# interlinkP2B.net
KiCad netlist of a schematic drawn in Altium Designer
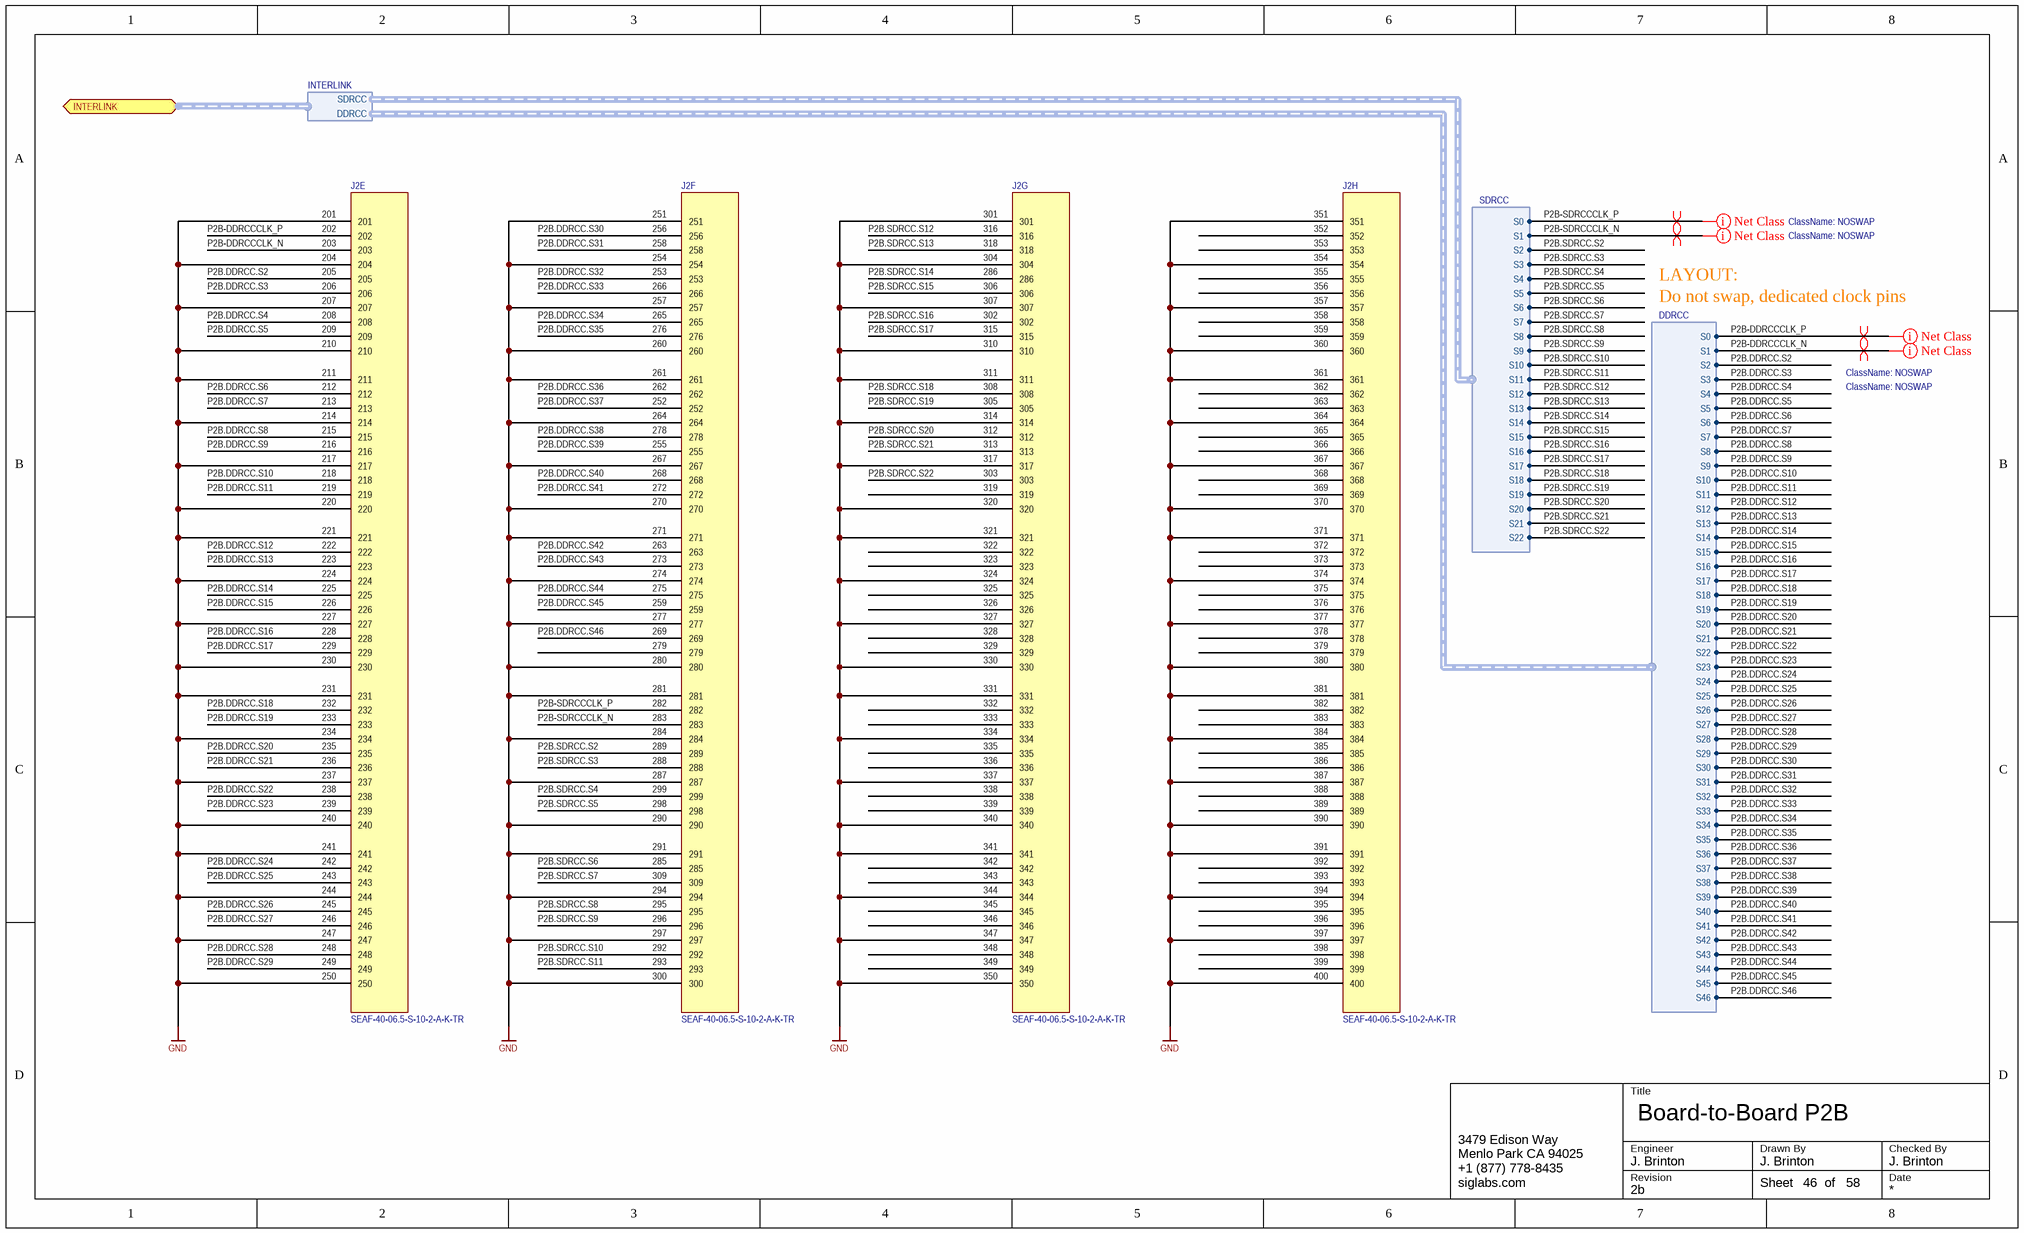
[diagram p0: interlinkP2B.SchDoc]

(export (version "E")
  (design (tool "Eeschema 10.0.6"))
  (components
    (comp (ref "J2")
      (value "SEAF-40-06.5-S-10-2-A-K-TR")
      (footprint "samtec:SEAF-40-06.5-S-10-2-A-K-TR")
      (description "Terminal Array Assembly, Surface Mount, 0.050\" Pitch, 400 Pins")
      (fields (field (name "MANUFACTURER") "Samtec"))
      (libsource (lib "samtec") (part "SEAF-40-06.5-S-10-2-A-K-TR"))
    )
  )
  (nets
    (net (code "4") (name "/P2B-DDRCCCLK_N") (class "Default")
      (node (ref "J2") (pin "203") (pinfunction "203_203") (pintype "passive"))
    )
    (net (code "5") (name "/P2B-DDRCCCLK_P") (class "Default")
      (node (ref "J2") (pin "202") (pinfunction "202_202") (pintype "passive"))
    )
    (net (code "6") (name "/P2B-SDRCCCLK_N") (class "Default")
      (node (ref "J2") (pin "283") (pinfunction "283_283") (pintype "passive"))
    )
    (net (code "7") (name "/P2B-SDRCCCLK_P") (class "Default")
      (node (ref "J2") (pin "282") (pinfunction "282_282") (pintype "passive"))
    )
    (net (code "8") (name "/P2B.DDRCC.S2") (class "Default")
      (node (ref "J2") (pin "205") (pinfunction "205_205") (pintype "passive"))
    )
    (net (code "9") (name "/P2B.DDRCC.S3") (class "Default")
      (node (ref "J2") (pin "206") (pinfunction "206_206") (pintype "passive"))
    )
    (net (code "10") (name "/P2B.DDRCC.S4") (class "Default")
      (node (ref "J2") (pin "208") (pinfunction "208_208") (pintype "passive"))
    )
    (net (code "11") (name "/P2B.DDRCC.S5") (class "Default")
      (node (ref "J2") (pin "209") (pinfunction "209_209") (pintype "passive"))
    )
    (net (code "12") (name "/P2B.DDRCC.S6") (class "Default")
      (node (ref "J2") (pin "212") (pinfunction "212_212") (pintype "passive"))
    )
    (net (code "13") (name "/P2B.DDRCC.S7") (class "Default")
      (node (ref "J2") (pin "213") (pinfunction "213_213") (pintype "passive"))
    )
    (net (code "14") (name "/P2B.DDRCC.S8") (class "Default")
      (node (ref "J2") (pin "215") (pinfunction "215_215") (pintype "passive"))
    )
    (net (code "15") (name "/P2B.DDRCC.S9") (class "Default")
      (node (ref "J2") (pin "216") (pinfunction "216_216") (pintype "passive"))
    )
    (net (code "16") (name "/P2B.DDRCC.S10") (class "Default")
      (node (ref "J2") (pin "218") (pinfunction "218_218") (pintype "passive"))
    )
    (net (code "17") (name "/P2B.DDRCC.S11") (class "Default")
      (node (ref "J2") (pin "219") (pinfunction "219_219") (pintype "passive"))
    )
    (net (code "18") (name "/P2B.DDRCC.S12") (class "Default")
      (node (ref "J2") (pin "222") (pinfunction "222_222") (pintype "passive"))
    )
    (net (code "19") (name "/P2B.DDRCC.S13") (class "Default")
      (node (ref "J2") (pin "223") (pinfunction "223_223") (pintype "passive"))
    )
    (net (code "20") (name "/P2B.DDRCC.S14") (class "Default")
      (node (ref "J2") (pin "225") (pinfunction "225_225") (pintype "passive"))
    )
    (net (code "21") (name "/P2B.DDRCC.S15") (class "Default")
      (node (ref "J2") (pin "226") (pinfunction "226_226") (pintype "passive"))
    )
    (net (code "22") (name "/P2B.DDRCC.S16") (class "Default")
      (node (ref "J2") (pin "228") (pinfunction "228_228") (pintype "passive"))
    )
    (net (code "23") (name "/P2B.DDRCC.S17") (class "Default")
      (node (ref "J2") (pin "229") (pinfunction "229_229") (pintype "passive"))
    )
    (net (code "24") (name "/P2B.DDRCC.S18") (class "Default")
      (node (ref "J2") (pin "232") (pinfunction "232_232") (pintype "passive"))
    )
    (net (code "25") (name "/P2B.DDRCC.S19") (class "Default")
      (node (ref "J2") (pin "233") (pinfunction "233_233") (pintype "passive"))
    )
    (net (code "26") (name "/P2B.DDRCC.S20") (class "Default")
      (node (ref "J2") (pin "235") (pinfunction "235_235") (pintype "passive"))
    )
    (net (code "27") (name "/P2B.DDRCC.S21") (class "Default")
      (node (ref "J2") (pin "236") (pinfunction "236_236") (pintype "passive"))
    )
    (net (code "28") (name "/P2B.DDRCC.S22") (class "Default")
      (node (ref "J2") (pin "238") (pinfunction "238_238") (pintype "passive"))
    )
    (net (code "29") (name "/P2B.DDRCC.S23") (class "Default")
      (node (ref "J2") (pin "239") (pinfunction "239_239") (pintype "passive"))
    )
    (net (code "30") (name "/P2B.DDRCC.S24") (class "Default")
      (node (ref "J2") (pin "242") (pinfunction "242_242") (pintype "passive"))
    )
    (net (code "31") (name "/P2B.DDRCC.S25") (class "Default")
      (node (ref "J2") (pin "243") (pinfunction "243_243") (pintype "passive"))
    )
    (net (code "32") (name "/P2B.DDRCC.S26") (class "Default")
      (node (ref "J2") (pin "245") (pinfunction "245_245") (pintype "passive"))
    )
    (net (code "33") (name "/P2B.DDRCC.S27") (class "Default")
      (node (ref "J2") (pin "246") (pinfunction "246_246") (pintype "passive"))
    )
    (net (code "34") (name "/P2B.DDRCC.S28") (class "Default")
      (node (ref "J2") (pin "248") (pinfunction "248_248") (pintype "passive"))
    )
    (net (code "35") (name "/P2B.DDRCC.S29") (class "Default")
      (node (ref "J2") (pin "249") (pinfunction "249_249") (pintype "passive"))
    )
    (net (code "36") (name "/P2B.DDRCC.S30") (class "Default")
      (node (ref "J2") (pin "256") (pinfunction "256_256") (pintype "passive"))
    )
    (net (code "37") (name "/P2B.DDRCC.S31") (class "Default")
      (node (ref "J2") (pin "258") (pinfunction "258_258") (pintype "passive"))
    )
    (net (code "38") (name "/P2B.DDRCC.S32") (class "Default")
      (node (ref "J2") (pin "253") (pinfunction "253_253") (pintype "passive"))
    )
    (net (code "39") (name "/P2B.DDRCC.S33") (class "Default")
      (node (ref "J2") (pin "266") (pinfunction "266_266") (pintype "passive"))
    )
    (net (code "40") (name "/P2B.DDRCC.S34") (class "Default")
      (node (ref "J2") (pin "265") (pinfunction "265_265") (pintype "passive"))
    )
    (net (code "41") (name "/P2B.DDRCC.S35") (class "Default")
      (node (ref "J2") (pin "276") (pinfunction "276_276") (pintype "passive"))
    )
    (net (code "42") (name "/P2B.DDRCC.S36") (class "Default")
      (node (ref "J2") (pin "262") (pinfunction "262_262") (pintype "passive"))
    )
    (net (code "43") (name "/P2B.DDRCC.S37") (class "Default")
      (node (ref "J2") (pin "252") (pinfunction "252_252") (pintype "passive"))
    )
    (net (code "44") (name "/P2B.DDRCC.S38") (class "Default")
      (node (ref "J2") (pin "278") (pinfunction "278_278") (pintype "passive"))
    )
    (net (code "45") (name "/P2B.DDRCC.S39") (class "Default")
      (node (ref "J2") (pin "255") (pinfunction "255_255") (pintype "passive"))
    )
    (net (code "46") (name "/P2B.DDRCC.S40") (class "Default")
      (node (ref "J2") (pin "268") (pinfunction "268_268") (pintype "passive"))
    )
    (net (code "47") (name "/P2B.DDRCC.S41") (class "Default")
      (node (ref "J2") (pin "272") (pinfunction "272_272") (pintype "passive"))
    )
    (net (code "48") (name "/P2B.DDRCC.S42") (class "Default")
      (node (ref "J2") (pin "263") (pinfunction "263_263") (pintype "passive"))
    )
    (net (code "49") (name "/P2B.DDRCC.S43") (class "Default")
      (node (ref "J2") (pin "273") (pinfunction "273_273") (pintype "passive"))
    )
    (net (code "50") (name "/P2B.DDRCC.S44") (class "Default")
      (node (ref "J2") (pin "275") (pinfunction "275_275") (pintype "passive"))
    )
    (net (code "51") (name "/P2B.DDRCC.S45") (class "Default")
      (node (ref "J2") (pin "259") (pinfunction "259_259") (pintype "passive"))
    )
    (net (code "52") (name "/P2B.DDRCC.S46") (class "Default")
      (node (ref "J2") (pin "269") (pinfunction "269_269") (pintype "passive"))
    )
    (net (code "53") (name "/P2B.SDRCC.S2") (class "Default")
      (node (ref "J2") (pin "289") (pinfunction "289_289") (pintype "passive"))
    )
    (net (code "54") (name "/P2B.SDRCC.S3") (class "Default")
      (node (ref "J2") (pin "288") (pinfunction "288_288") (pintype "passive"))
    )
    (net (code "55") (name "/P2B.SDRCC.S4") (class "Default")
      (node (ref "J2") (pin "299") (pinfunction "299_299") (pintype "passive"))
    )
    (net (code "56") (name "/P2B.SDRCC.S5") (class "Default")
      (node (ref "J2") (pin "298") (pinfunction "298_298") (pintype "passive"))
    )
    (net (code "57") (name "/P2B.SDRCC.S6") (class "Default")
      (node (ref "J2") (pin "285") (pinfunction "285_285") (pintype "passive"))
    )
    (net (code "58") (name "/P2B.SDRCC.S7") (class "Default")
      (node (ref "J2") (pin "309") (pinfunction "309_309") (pintype "passive"))
    )
    (net (code "59") (name "/P2B.SDRCC.S8") (class "Default")
      (node (ref "J2") (pin "295") (pinfunction "295_295") (pintype "passive"))
    )
    (net (code "60") (name "/P2B.SDRCC.S9") (class "Default")
      (node (ref "J2") (pin "296") (pinfunction "296_296") (pintype "passive"))
    )
    (net (code "61") (name "/P2B.SDRCC.S10") (class "Default")
      (node (ref "J2") (pin "292") (pinfunction "292_292") (pintype "passive"))
    )
    (net (code "62") (name "/P2B.SDRCC.S11") (class "Default")
      (node (ref "J2") (pin "293") (pinfunction "293_293") (pintype "passive"))
    )
    (net (code "63") (name "/P2B.SDRCC.S12") (class "Default")
      (node (ref "J2") (pin "316") (pinfunction "316_316") (pintype "passive"))
    )
    (net (code "64") (name "/P2B.SDRCC.S13") (class "Default")
      (node (ref "J2") (pin "318") (pinfunction "318_318") (pintype "passive"))
    )
    (net (code "65") (name "/P2B.SDRCC.S14") (class "Default")
      (node (ref "J2") (pin "286") (pinfunction "286_286") (pintype "passive"))
    )
    (net (code "66") (name "/P2B.SDRCC.S15") (class "Default")
      (node (ref "J2") (pin "306") (pinfunction "306_306") (pintype "passive"))
    )
    (net (code "67") (name "/P2B.SDRCC.S16") (class "Default")
      (node (ref "J2") (pin "302") (pinfunction "302_302") (pintype "passive"))
    )
    (net (code "68") (name "/P2B.SDRCC.S17") (class "Default")
      (node (ref "J2") (pin "315") (pinfunction "315_315") (pintype "passive"))
    )
    (net (code "69") (name "/P2B.SDRCC.S18") (class "Default")
      (node (ref "J2") (pin "308") (pinfunction "308_308") (pintype "passive"))
    )
    (net (code "70") (name "/P2B.SDRCC.S19") (class "Default")
      (node (ref "J2") (pin "305") (pinfunction "305_305") (pintype "passive"))
    )
    (net (code "71") (name "/P2B.SDRCC.S20") (class "Default")
      (node (ref "J2") (pin "312") (pinfunction "312_312") (pintype "passive"))
    )
    (net (code "72") (name "/P2B.SDRCC.S21") (class "Default")
      (node (ref "J2") (pin "313") (pinfunction "313_313") (pintype "passive"))
    )
    (net (code "73") (name "/P2B.SDRCC.S22") (class "Default")
      (node (ref "J2") (pin "303") (pinfunction "303_303") (pintype "passive"))
    )
    (net (code "77") (name "GND") (class "Default")
      (node (ref "J2") (pin "201") (pinfunction "201_201") (pintype "passive"))
      (node (ref "J2") (pin "204") (pinfunction "204_204") (pintype "passive"))
      (node (ref "J2") (pin "207") (pinfunction "207_207") (pintype "passive"))
      (node (ref "J2") (pin "210") (pinfunction "210_210") (pintype "passive"))
      (node (ref "J2") (pin "211") (pinfunction "211_211") (pintype "passive"))
      (node (ref "J2") (pin "214") (pinfunction "214_214") (pintype "passive"))
      (node (ref "J2") (pin "217") (pinfunction "217_217") (pintype "passive"))
      (node (ref "J2") (pin "220") (pinfunction "220_220") (pintype "passive"))
      (node (ref "J2") (pin "221") (pinfunction "221_221") (pintype "passive"))
      (node (ref "J2") (pin "224") (pinfunction "224_224") (pintype "passive"))
      (node (ref "J2") (pin "227") (pinfunction "227_227") (pintype "passive"))
      (node (ref "J2") (pin "230") (pinfunction "230_230") (pintype "passive"))
      (node (ref "J2") (pin "231") (pinfunction "231_231") (pintype "passive"))
      (node (ref "J2") (pin "234") (pinfunction "234_234") (pintype "passive"))
      (node (ref "J2") (pin "237") (pinfunction "237_237") (pintype "passive"))
      (node (ref "J2") (pin "240") (pinfunction "240_240") (pintype "passive"))
      (node (ref "J2") (pin "241") (pinfunction "241_241") (pintype "passive"))
      (node (ref "J2") (pin "244") (pinfunction "244_244") (pintype "passive"))
      (node (ref "J2") (pin "247") (pinfunction "247_247") (pintype "passive"))
      (node (ref "J2") (pin "250") (pinfunction "250_250") (pintype "passive"))
      (node (ref "J2") (pin "251") (pinfunction "251_251") (pintype "passive"))
      (node (ref "J2") (pin "254") (pinfunction "254_254") (pintype "passive"))
      (node (ref "J2") (pin "257") (pinfunction "257_257") (pintype "passive"))
      (node (ref "J2") (pin "260") (pinfunction "260_260") (pintype "passive"))
      (node (ref "J2") (pin "261") (pinfunction "261_261") (pintype "passive"))
      (node (ref "J2") (pin "264") (pinfunction "264_264") (pintype "passive"))
      (node (ref "J2") (pin "267") (pinfunction "267_267") (pintype "passive"))
      (node (ref "J2") (pin "270") (pinfunction "270_270") (pintype "passive"))
      (node (ref "J2") (pin "271") (pinfunction "271_271") (pintype "passive"))
      (node (ref "J2") (pin "274") (pinfunction "274_274") (pintype "passive"))
      (node (ref "J2") (pin "277") (pinfunction "277_277") (pintype "passive"))
      (node (ref "J2") (pin "280") (pinfunction "280_280") (pintype "passive"))
      (node (ref "J2") (pin "281") (pinfunction "281_281") (pintype "passive"))
      (node (ref "J2") (pin "284") (pinfunction "284_284") (pintype "passive"))
      (node (ref "J2") (pin "287") (pinfunction "287_287") (pintype "passive"))
      (node (ref "J2") (pin "290") (pinfunction "290_290") (pintype "passive"))
      (node (ref "J2") (pin "291") (pinfunction "291_291") (pintype "passive"))
      (node (ref "J2") (pin "294") (pinfunction "294_294") (pintype "passive"))
      (node (ref "J2") (pin "297") (pinfunction "297_297") (pintype "passive"))
      (node (ref "J2") (pin "300") (pinfunction "300_300") (pintype "passive"))
      (node (ref "J2") (pin "301") (pinfunction "301_301") (pintype "passive"))
      (node (ref "J2") (pin "304") (pinfunction "304_304") (pintype "passive"))
      (node (ref "J2") (pin "307") (pinfunction "307_307") (pintype "passive"))
      (node (ref "J2") (pin "310") (pinfunction "310_310") (pintype "passive"))
      (node (ref "J2") (pin "311") (pinfunction "311_311") (pintype "passive"))
      (node (ref "J2") (pin "314") (pinfunction "314_314") (pintype "passive"))
      (node (ref "J2") (pin "317") (pinfunction "317_317") (pintype "passive"))
      (node (ref "J2") (pin "320") (pinfunction "320_320") (pintype "passive"))
      (node (ref "J2") (pin "321") (pinfunction "321_321") (pintype "passive"))
      (node (ref "J2") (pin "324") (pinfunction "324_324") (pintype "passive"))
      (node (ref "J2") (pin "327") (pinfunction "327_327") (pintype "passive"))
      (node (ref "J2") (pin "330") (pinfunction "330_330") (pintype "passive"))
      (node (ref "J2") (pin "331") (pinfunction "331_331") (pintype "passive"))
      (node (ref "J2") (pin "334") (pinfunction "334_334") (pintype "passive"))
      (node (ref "J2") (pin "337") (pinfunction "337_337") (pintype "passive"))
      (node (ref "J2") (pin "340") (pinfunction "340_340") (pintype "passive"))
      (node (ref "J2") (pin "341") (pinfunction "341_341") (pintype "passive"))
      (node (ref "J2") (pin "344") (pinfunction "344_344") (pintype "passive"))
      (node (ref "J2") (pin "347") (pinfunction "347_347") (pintype "passive"))
      (node (ref "J2") (pin "350") (pinfunction "350_350") (pintype "passive"))
      (node (ref "J2") (pin "351") (pinfunction "351_351") (pintype "passive"))
      (node (ref "J2") (pin "354") (pinfunction "354_354") (pintype "passive"))
      (node (ref "J2") (pin "357") (pinfunction "357_357") (pintype "passive"))
      (node (ref "J2") (pin "360") (pinfunction "360_360") (pintype "passive"))
      (node (ref "J2") (pin "361") (pinfunction "361_361") (pintype "passive"))
      (node (ref "J2") (pin "364") (pinfunction "364_364") (pintype "passive"))
      (node (ref "J2") (pin "367") (pinfunction "367_367") (pintype "passive"))
      (node (ref "J2") (pin "370") (pinfunction "370_370") (pintype "passive"))
      (node (ref "J2") (pin "371") (pinfunction "371_371") (pintype "passive"))
      (node (ref "J2") (pin "374") (pinfunction "374_374") (pintype "passive"))
      (node (ref "J2") (pin "377") (pinfunction "377_377") (pintype "passive"))
      (node (ref "J2") (pin "380") (pinfunction "380_380") (pintype "passive"))
      (node (ref "J2") (pin "381") (pinfunction "381_381") (pintype "passive"))
      (node (ref "J2") (pin "384") (pinfunction "384_384") (pintype "passive"))
      (node (ref "J2") (pin "387") (pinfunction "387_387") (pintype "passive"))
      (node (ref "J2") (pin "390") (pinfunction "390_390") (pintype "passive"))
      (node (ref "J2") (pin "391") (pinfunction "391_391") (pintype "passive"))
      (node (ref "J2") (pin "394") (pinfunction "394_394") (pintype "passive"))
      (node (ref "J2") (pin "397") (pinfunction "397_397") (pintype "passive"))
      (node (ref "J2") (pin "400") (pinfunction "400_400") (pintype "passive"))
    )
    (net (code "78") (name "unconnected-(J2-Pad279)") (class "Default")
      (node (ref "J2") (pin "279") (pinfunction "279_279") (pintype "passive"))
    )
    (net (code "79") (name "unconnected-(J2-Pad319)") (class "Default")
      (node (ref "J2") (pin "319") (pinfunction "319_319") (pintype "passive"))
    )
    (net (code "80") (name "unconnected-(J2-Pad322)") (class "Default")
      (node (ref "J2") (pin "322") (pinfunction "322_322") (pintype "passive"))
    )
    (net (code "81") (name "unconnected-(J2-Pad323)") (class "Default")
      (node (ref "J2") (pin "323") (pinfunction "323_323") (pintype "passive"))
    )
    (net (code "82") (name "unconnected-(J2-Pad325)") (class "Default")
      (node (ref "J2") (pin "325") (pinfunction "325_325") (pintype "passive"))
    )
    (net (code "83") (name "unconnected-(J2-Pad326)") (class "Default")
      (node (ref "J2") (pin "326") (pinfunction "326_326") (pintype "passive"))
    )
    (net (code "84") (name "unconnected-(J2-Pad328)") (class "Default")
      (node (ref "J2") (pin "328") (pinfunction "328_328") (pintype "passive"))
    )
    (net (code "85") (name "unconnected-(J2-Pad329)") (class "Default")
      (node (ref "J2") (pin "329") (pinfunction "329_329") (pintype "passive"))
    )
    (net (code "86") (name "unconnected-(J2-Pad332)") (class "Default")
      (node (ref "J2") (pin "332") (pinfunction "332_332") (pintype "passive"))
    )
    (net (code "87") (name "unconnected-(J2-Pad333)") (class "Default")
      (node (ref "J2") (pin "333") (pinfunction "333_333") (pintype "passive"))
    )
    (net (code "88") (name "unconnected-(J2-Pad335)") (class "Default")
      (node (ref "J2") (pin "335") (pinfunction "335_335") (pintype "passive"))
    )
    (net (code "89") (name "unconnected-(J2-Pad336)") (class "Default")
      (node (ref "J2") (pin "336") (pinfunction "336_336") (pintype "passive"))
    )
    (net (code "90") (name "unconnected-(J2-Pad338)") (class "Default")
      (node (ref "J2") (pin "338") (pinfunction "338_338") (pintype "passive"))
    )
    (net (code "91") (name "unconnected-(J2-Pad339)") (class "Default")
      (node (ref "J2") (pin "339") (pinfunction "339_339") (pintype "passive"))
    )
    (net (code "92") (name "unconnected-(J2-Pad342)") (class "Default")
      (node (ref "J2") (pin "342") (pinfunction "342_342") (pintype "passive"))
    )
    (net (code "93") (name "unconnected-(J2-Pad343)") (class "Default")
      (node (ref "J2") (pin "343") (pinfunction "343_343") (pintype "passive"))
    )
    (net (code "94") (name "unconnected-(J2-Pad345)") (class "Default")
      (node (ref "J2") (pin "345") (pinfunction "345_345") (pintype "passive"))
    )
    (net (code "95") (name "unconnected-(J2-Pad346)") (class "Default")
      (node (ref "J2") (pin "346") (pinfunction "346_346") (pintype "passive"))
    )
    (net (code "96") (name "unconnected-(J2-Pad348)") (class "Default")
      (node (ref "J2") (pin "348") (pinfunction "348_348") (pintype "passive"))
    )
    (net (code "97") (name "unconnected-(J2-Pad349)") (class "Default")
      (node (ref "J2") (pin "349") (pinfunction "349_349") (pintype "passive"))
    )
    (net (code "98") (name "unconnected-(J2-Pad352)") (class "Default")
      (node (ref "J2") (pin "352") (pinfunction "352_352") (pintype "passive"))
    )
    (net (code "99") (name "unconnected-(J2-Pad353)") (class "Default")
      (node (ref "J2") (pin "353") (pinfunction "353_353") (pintype "passive"))
    )
    (net (code "100") (name "unconnected-(J2-Pad355)") (class "Default")
      (node (ref "J2") (pin "355") (pinfunction "355_355") (pintype "passive"))
    )
    (net (code "101") (name "unconnected-(J2-Pad356)") (class "Default")
      (node (ref "J2") (pin "356") (pinfunction "356_356") (pintype "passive"))
    )
    (net (code "102") (name "unconnected-(J2-Pad358)") (class "Default")
      (node (ref "J2") (pin "358") (pinfunction "358_358") (pintype "passive"))
    )
    (net (code "103") (name "unconnected-(J2-Pad359)") (class "Default")
      (node (ref "J2") (pin "359") (pinfunction "359_359") (pintype "passive"))
    )
    (net (code "104") (name "unconnected-(J2-Pad362)") (class "Default")
      (node (ref "J2") (pin "362") (pinfunction "362_362") (pintype "passive"))
    )
    (net (code "105") (name "unconnected-(J2-Pad363)") (class "Default")
      (node (ref "J2") (pin "363") (pinfunction "363_363") (pintype "passive"))
    )
    (net (code "106") (name "unconnected-(J2-Pad365)") (class "Default")
      (node (ref "J2") (pin "365") (pinfunction "365_365") (pintype "passive"))
    )
    (net (code "107") (name "unconnected-(J2-Pad366)") (class "Default")
      (node (ref "J2") (pin "366") (pinfunction "366_366") (pintype "passive"))
    )
    (net (code "108") (name "unconnected-(J2-Pad368)") (class "Default")
      (node (ref "J2") (pin "368") (pinfunction "368_368") (pintype "passive"))
    )
    (net (code "109") (name "unconnected-(J2-Pad369)") (class "Default")
      (node (ref "J2") (pin "369") (pinfunction "369_369") (pintype "passive"))
    )
    (net (code "110") (name "unconnected-(J2-Pad372)") (class "Default")
      (node (ref "J2") (pin "372") (pinfunction "372_372") (pintype "passive"))
    )
    (net (code "111") (name "unconnected-(J2-Pad373)") (class "Default")
      (node (ref "J2") (pin "373") (pinfunction "373_373") (pintype "passive"))
    )
    (net (code "112") (name "unconnected-(J2-Pad375)") (class "Default")
      (node (ref "J2") (pin "375") (pinfunction "375_375") (pintype "passive"))
    )
    (net (code "113") (name "unconnected-(J2-Pad376)") (class "Default")
      (node (ref "J2") (pin "376") (pinfunction "376_376") (pintype "passive"))
    )
    (net (code "114") (name "unconnected-(J2-Pad378)") (class "Default")
      (node (ref "J2") (pin "378") (pinfunction "378_378") (pintype "passive"))
    )
    (net (code "115") (name "unconnected-(J2-Pad379)") (class "Default")
      (node (ref "J2") (pin "379") (pinfunction "379_379") (pintype "passive"))
    )
    (net (code "116") (name "unconnected-(J2-Pad382)") (class "Default")
      (node (ref "J2") (pin "382") (pinfunction "382_382") (pintype "passive"))
    )
    (net (code "117") (name "unconnected-(J2-Pad383)") (class "Default")
      (node (ref "J2") (pin "383") (pinfunction "383_383") (pintype "passive"))
    )
    (net (code "118") (name "unconnected-(J2-Pad385)") (class "Default")
      (node (ref "J2") (pin "385") (pinfunction "385_385") (pintype "passive"))
    )
    (net (code "119") (name "unconnected-(J2-Pad386)") (class "Default")
      (node (ref "J2") (pin "386") (pinfunction "386_386") (pintype "passive"))
    )
    (net (code "120") (name "unconnected-(J2-Pad388)") (class "Default")
      (node (ref "J2") (pin "388") (pinfunction "388_388") (pintype "passive"))
    )
    (net (code "121") (name "unconnected-(J2-Pad389)") (class "Default")
      (node (ref "J2") (pin "389") (pinfunction "389_389") (pintype "passive"))
    )
    (net (code "122") (name "unconnected-(J2-Pad392)") (class "Default")
      (node (ref "J2") (pin "392") (pinfunction "392_392") (pintype "passive"))
    )
    (net (code "123") (name "unconnected-(J2-Pad393)") (class "Default")
      (node (ref "J2") (pin "393") (pinfunction "393_393") (pintype "passive"))
    )
    (net (code "124") (name "unconnected-(J2-Pad395)") (class "Default")
      (node (ref "J2") (pin "395") (pinfunction "395_395") (pintype "passive"))
    )
    (net (code "125") (name "unconnected-(J2-Pad396)") (class "Default")
      (node (ref "J2") (pin "396") (pinfunction "396_396") (pintype "passive"))
    )
    (net (code "126") (name "unconnected-(J2-Pad398)") (class "Default")
      (node (ref "J2") (pin "398") (pinfunction "398_398") (pintype "passive"))
    )
    (net (code "127") (name "unconnected-(J2-Pad399)") (class "Default")
      (node (ref "J2") (pin "399") (pinfunction "399_399") (pintype "passive"))
    )
  )
)
